# Cat_Laser.net
KiCad netlist of a schematic drawn in EAGLE
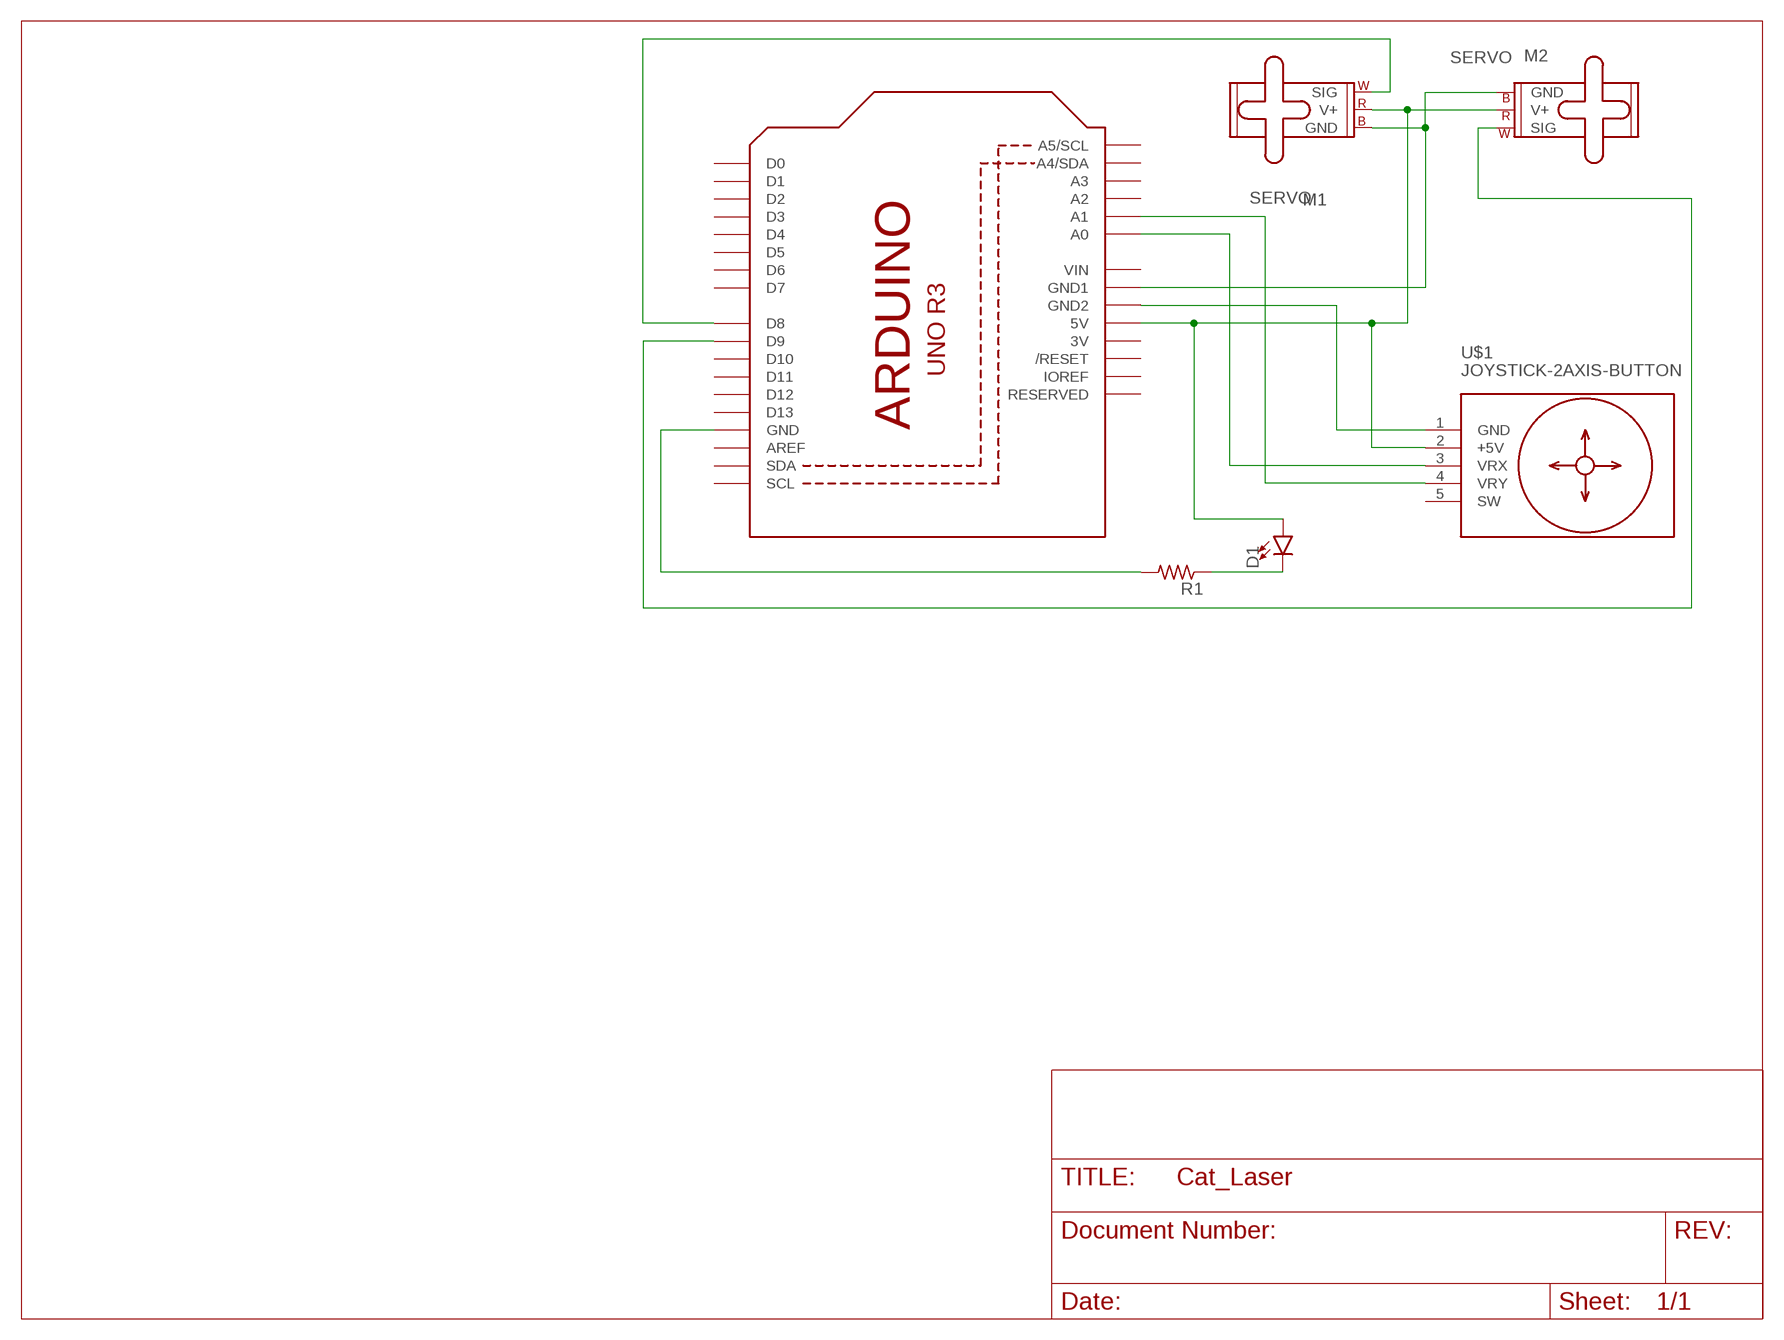
[diagram p0: schematic, sheet 1]

(export (version "E")
  (design (tool "Eeschema 10.0.6"))
  (components
    (comp (ref "D1")
      (value "LED3MM")
      (footprint "eagle-import:LED_3MM")
      (libsource (lib "eagle-import") (part "LED3MM"))
    )
    (comp (ref "M1")
      (value "SERVO")
      (footprint "eagle-import:1X03")
      (libsource (lib "eagle-import") (part "SERVO"))
    )
    (comp (ref "M2")
      (value "SERVO")
      (footprint "eagle-import:1X03")
      (libsource (lib "eagle-import") (part "SERVO"))
    )
    (comp (ref "R1")
      (value "FLIPFLOP-RES")
      (footprint "eagle-import:0805-THM")
      (libsource (lib "eagle-import") (part "FLIPFLOP-RES"))
    )
    (comp (ref "U$1")
      (value "JOYSTICK-2AXIS-BUTTON")
      (footprint "eagle-import:JOYSTICK-2AXIS-BUTTON")
      (libsource (lib "eagle-import") (part "JOYSTICK-2AXIS-BUTTON"))
    )
    (comp (ref "U1")
      (value "ARDUINOR3-BPLACE")
      (footprint "eagle-import:ARDUINOR3-BPLACE")
      (libsource (lib "eagle-import") (part "ARDUINOR3-BPLACE"))
    )
  )
  (nets
    (net (code "1") (name "/3V") (class "Default")
      (node (ref "U1") (pin "3V") (pinfunction "3V_3V") (pintype "power_in"))
    )
    (net (code "2") (name "/VIN") (class "Default")
      (node (ref "U1") (pin "VIN") (pinfunction "VIN_VIN") (pintype "power_in"))
    )
    (net (code "3") (name "Net-(D1-C)") (class "Default")
      (node (ref "D1") (pin "K") (pinfunction "C_K") (pintype "passive"))
      (node (ref "R1") (pin "1") (pinfunction "1_1") (pintype "passive"))
    )
    (net (code "4") (name "Net-(M1-GND)") (class "Default")
      (node (ref "M1") (pin "3") (pinfunction "GND_3") (pintype "bidirectional"))
      (node (ref "M2") (pin "3") (pinfunction "GND_3") (pintype "bidirectional"))
      (node (ref "U1") (pin "GND1") (pinfunction "GND1_GND1") (pintype "power_in"))
    )
    (net (code "5") (name "Net-(M1-SIG)") (class "Default")
      (node (ref "M1") (pin "1") (pinfunction "SIG_1") (pintype "bidirectional"))
      (node (ref "U1") (pin "D8") (pinfunction "D8_D8") (pintype "bidirectional"))
    )
    (net (code "6") (name "Net-(M1-V+)") (class "Default")
      (node (ref "D1") (pin "A") (pinfunction "A_A") (pintype "passive"))
      (node (ref "M1") (pin "2") (pinfunction "V+_2") (pintype "bidirectional"))
      (node (ref "M2") (pin "2") (pinfunction "V+_2") (pintype "bidirectional"))
      (node (ref "U$1") (pin "2") (pinfunction "+5V_2") (pintype "power_in"))
      (node (ref "U1") (pin "5V") (pinfunction "5V_5V") (pintype "power_in"))
    )
    (net (code "7") (name "Net-(M2-SIG)") (class "Default")
      (node (ref "M2") (pin "1") (pinfunction "SIG_1") (pintype "bidirectional"))
      (node (ref "U1") (pin "D9") (pinfunction "D9_D9") (pintype "bidirectional"))
    )
    (net (code "8") (name "Net-(R1-Pad2)") (class "Default")
      (node (ref "R1") (pin "2") (pinfunction "2_2") (pintype "passive"))
      (node (ref "U1") (pin "GND") (pinfunction "GND_GND") (pintype "power_in"))
    )
    (net (code "9") (name "Net-(U$1-GND)") (class "Default")
      (node (ref "U$1") (pin "1") (pinfunction "GND_1") (pintype "power_in"))
      (node (ref "U1") (pin "GND2") (pinfunction "GND2_GND2") (pintype "power_in"))
    )
    (net (code "10") (name "Net-(U$1-VRX)") (class "Default")
      (node (ref "U$1") (pin "3") (pinfunction "VRX_3") (pintype "passive"))
      (node (ref "U1") (pin "A0") (pinfunction "A0_A0") (pintype "bidirectional"))
    )
    (net (code "11") (name "Net-(U$1-VRY)") (class "Default")
      (node (ref "U$1") (pin "4") (pinfunction "VRY_4") (pintype "passive"))
      (node (ref "U1") (pin "A1") (pinfunction "A1_A1") (pintype "bidirectional"))
    )
    (net (code "12") (name "unconnected-(U$1-SW-Pad5)") (class "Default")
      (node (ref "U$1") (pin "5") (pinfunction "SW_5") (pintype "passive"))
    )
    (net (code "13") (name "unconnected-(U1-A4{slash}SDA-PadA4)") (class "Default")
      (node (ref "U1") (pin "A4") (pinfunction "A4/SDA_A4") (pintype "bidirectional"))
    )
    (net (code "14") (name "unconnected-(U1-A5{slash}SCL-PadA5)") (class "Default")
      (node (ref "U1") (pin "A5") (pinfunction "A5/SCL_A5") (pintype "bidirectional"))
    )
    (net (code "15") (name "unconnected-(U1-PadA2)") (class "Default")
      (node (ref "U1") (pin "A2") (pinfunction "A2_A2") (pintype "bidirectional"))
    )
    (net (code "16") (name "unconnected-(U1-PadA3)") (class "Default")
      (node (ref "U1") (pin "A3") (pinfunction "A3_A3") (pintype "bidirectional"))
    )
    (net (code "17") (name "unconnected-(U1-PadAREF)") (class "Default")
      (node (ref "U1") (pin "AREF") (pinfunction "AREF_AREF") (pintype "bidirectional"))
    )
    (net (code "18") (name "unconnected-(U1-PadD0)") (class "Default")
      (node (ref "U1") (pin "D0") (pinfunction "D0_D0") (pintype "bidirectional"))
    )
    (net (code "19") (name "unconnected-(U1-PadD1)") (class "Default")
      (node (ref "U1") (pin "D1") (pinfunction "D1_D1") (pintype "bidirectional"))
    )
    (net (code "20") (name "unconnected-(U1-PadD2)") (class "Default")
      (node (ref "U1") (pin "D2") (pinfunction "D2_D2") (pintype "bidirectional"))
    )
    (net (code "21") (name "unconnected-(U1-PadD3)") (class "Default")
      (node (ref "U1") (pin "D3") (pinfunction "D3_D3") (pintype "bidirectional"))
    )
    (net (code "22") (name "unconnected-(U1-PadD4)") (class "Default")
      (node (ref "U1") (pin "D4") (pinfunction "D4_D4") (pintype "bidirectional"))
    )
    (net (code "23") (name "unconnected-(U1-PadD5)") (class "Default")
      (node (ref "U1") (pin "D5") (pinfunction "D5_D5") (pintype "bidirectional"))
    )
    (net (code "24") (name "unconnected-(U1-PadD6)") (class "Default")
      (node (ref "U1") (pin "D6") (pinfunction "D6_D6") (pintype "bidirectional"))
    )
    (net (code "25") (name "unconnected-(U1-PadD7)") (class "Default")
      (node (ref "U1") (pin "D7") (pinfunction "D7_D7") (pintype "bidirectional"))
    )
    (net (code "26") (name "unconnected-(U1-PadD10)") (class "Default")
      (node (ref "U1") (pin "D10") (pinfunction "D10_D10") (pintype "bidirectional"))
    )
    (net (code "27") (name "unconnected-(U1-PadD11)") (class "Default")
      (node (ref "U1") (pin "D11") (pinfunction "D11_D11") (pintype "bidirectional"))
    )
    (net (code "28") (name "unconnected-(U1-PadD12)") (class "Default")
      (node (ref "U1") (pin "D12") (pinfunction "D12_D12") (pintype "bidirectional"))
    )
    (net (code "29") (name "unconnected-(U1-PadD13)") (class "Default")
      (node (ref "U1") (pin "D13") (pinfunction "D13_D13") (pintype "bidirectional"))
    )
    (net (code "30") (name "unconnected-(U1-PadIOREF)") (class "Default")
      (node (ref "U1") (pin "IOREF") (pinfunction "IOREF_IOREF") (pintype "output"))
    )
    (net (code "31") (name "unconnected-(U1-PadRESERVED)") (class "Default")
      (node (ref "U1") (pin "RESERVED") (pinfunction "RESERVED_RESERVED") (pintype "no_connect"))
    )
    (net (code "32") (name "unconnected-(U1-PadSCL)") (class "Default")
      (node (ref "U1") (pin "SCL") (pinfunction "SCL_SCL") (pintype "bidirectional"))
    )
    (net (code "33") (name "unconnected-(U1-PadSDA)") (class "Default")
      (node (ref "U1") (pin "SDA") (pinfunction "SDA_SDA") (pintype "bidirectional"))
    )
    (net (code "34") (name "unconnected-(U1-{slash}RESET-PadRESET)") (class "Default")
      (node (ref "U1") (pin "RESET") (pinfunction "/RESET_RESET") (pintype "bidirectional"))
    )
  )
)
